# CD_Welder.net
KiCad netlist of a schematic drawn in EAGLE
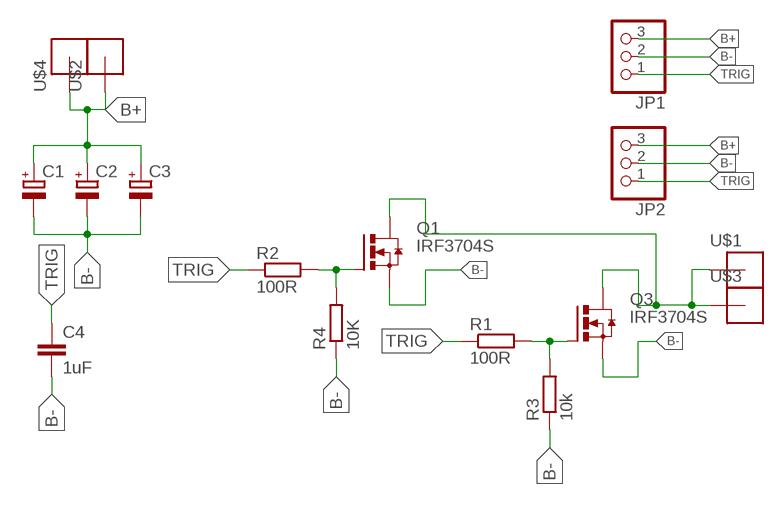
[diagram p0: schematic, sheet 1]

(export (version "E")
  (design (tool "Eeschema 10.0.6"))
  (components
    (comp (ref "C1")
      (value "CPOL-EUE10-30")
      (footprint "eagle-import:EB30D")
      (libsource (lib "eagle-import") (part "CPOL-EUE10-30"))
    )
    (comp (ref "C2")
      (value "CPOL-EUE10-30")
      (footprint "eagle-import:EB30D")
      (libsource (lib "eagle-import") (part "CPOL-EUE10-30"))
    )
    (comp (ref "C3")
      (value "CPOL-EUE10-30")
      (footprint "eagle-import:EB30D")
      (libsource (lib "eagle-import") (part "CPOL-EUE10-30"))
    )
    (comp (ref "C4")
      (value "1uF")
      (footprint "eagle-import:C1206")
      (libsource (lib "eagle-import") (part "C-EUC1206"))
    )
    (comp (ref "JP1")
      (value "PINHD-1X3")
      (footprint "eagle-import:1X03")
      (libsource (lib "eagle-import") (part "PINHD-1X3"))
    )
    (comp (ref "JP2")
      (value "PINHD-1X3")
      (footprint "eagle-import:1X03")
      (libsource (lib "eagle-import") (part "PINHD-1X3"))
    )
    (comp (ref "Q1")
      (value "IRF3704S")
      (footprint "eagle-import:D2PACK")
      (libsource (lib "eagle-import") (part "IRF3704S"))
    )
    (comp (ref "Q3")
      (value "IRF3704S")
      (footprint "eagle-import:D2PACK")
      (libsource (lib "eagle-import") (part "IRF3704S"))
    )
    (comp (ref "R1")
      (value "100R")
      (footprint "eagle-import:R1206")
      (libsource (lib "eagle-import") (part "R-EU_R1206"))
    )
    (comp (ref "R2")
      (value "100R")
      (footprint "eagle-import:R1206")
      (libsource (lib "eagle-import") (part "R-EU_R1206"))
    )
    (comp (ref "R3")
      (value "10k")
      (footprint "eagle-import:R1206")
      (libsource (lib "eagle-import") (part "R-EU_R1206"))
    )
    (comp (ref "R4")
      (value "10K")
      (footprint "eagle-import:R1206")
      (libsource (lib "eagle-import") (part "R-EU_R1206"))
    )
    (comp (ref "U$1")
      (value "BIG_PINHEADX1M4")
      (footprint "eagle-import:M4_PINHEAD")
      (libsource (lib "eagle-import") (part "BIG_PINHEADX1M4"))
    )
    (comp (ref "U$2")
      (value "BIG_PINHEADX1M4")
      (footprint "eagle-import:M4_PINHEAD")
      (libsource (lib "eagle-import") (part "BIG_PINHEADX1M4"))
    )
    (comp (ref "U$3")
      (value "BIG_PINHEADX1M4")
      (footprint "eagle-import:M4_PINHEAD")
      (libsource (lib "eagle-import") (part "BIG_PINHEADX1M4"))
    )
    (comp (ref "U$4")
      (value "BIG_PINHEADX1M4")
      (footprint "eagle-import:M4_PINHEAD")
      (libsource (lib "eagle-import") (part "BIG_PINHEADX1M4"))
    )
  )
  (nets
    (net (code "1") (name "B+") (class "Default")
      (node (ref "C1") (pin "+") (pinfunction "+_+") (pintype "passive"))
      (node (ref "C2") (pin "+") (pinfunction "+_+") (pintype "passive"))
      (node (ref "C3") (pin "+") (pinfunction "+_+") (pintype "passive"))
      (node (ref "JP1") (pin "3") (pinfunction "3_3") (pintype "passive"))
      (node (ref "JP2") (pin "3") (pinfunction "3_3") (pintype "passive"))
      (node (ref "U$2") (pin "P$1") (pinfunction "P$1_P$1") (pintype "bidirectional"))
      (node (ref "U$4") (pin "P$1") (pinfunction "P$1_P$1") (pintype "bidirectional"))
    )
    (net (code "2") (name "B-") (class "Default")
      (node (ref "C1") (pin "-") (pinfunction "-_-") (pintype "passive"))
      (node (ref "C2") (pin "-") (pinfunction "-_-") (pintype "passive"))
      (node (ref "C3") (pin "-") (pinfunction "-_-") (pintype "passive"))
      (node (ref "C4") (pin "2") (pinfunction "2_2") (pintype "passive"))
      (node (ref "JP1") (pin "2") (pinfunction "2_2") (pintype "passive"))
      (node (ref "JP2") (pin "2") (pinfunction "2_2") (pintype "passive"))
      (node (ref "Q1") (pin "3") (pinfunction "S_3") (pintype "passive"))
      (node (ref "Q3") (pin "3") (pinfunction "S_3") (pintype "passive"))
      (node (ref "R3") (pin "1") (pinfunction "1_1") (pintype "passive"))
      (node (ref "R4") (pin "1") (pinfunction "1_1") (pintype "passive"))
    )
    (net (code "3") (name "Net-(Q1-D)") (class "Default")
      (node (ref "Q1") (pin "2") (pinfunction "D_2") (pintype "passive"))
      (node (ref "Q3") (pin "2") (pinfunction "D_2") (pintype "passive"))
      (node (ref "U$1") (pin "P$1") (pinfunction "P$1_P$1") (pintype "bidirectional"))
      (node (ref "U$3") (pin "P$1") (pinfunction "P$1_P$1") (pintype "bidirectional"))
    )
    (net (code "4") (name "Net-(Q1-G)") (class "Default")
      (node (ref "Q1") (pin "1") (pinfunction "G_1") (pintype "passive"))
      (node (ref "R2") (pin "2") (pinfunction "2_2") (pintype "passive"))
      (node (ref "R4") (pin "2") (pinfunction "2_2") (pintype "passive"))
    )
    (net (code "5") (name "Net-(Q3-G)") (class "Default")
      (node (ref "Q3") (pin "1") (pinfunction "G_1") (pintype "passive"))
      (node (ref "R1") (pin "2") (pinfunction "2_2") (pintype "passive"))
      (node (ref "R3") (pin "2") (pinfunction "2_2") (pintype "passive"))
    )
    (net (code "6") (name "TRIG") (class "Default")
      (node (ref "C4") (pin "1") (pinfunction "1_1") (pintype "passive"))
      (node (ref "JP1") (pin "1") (pinfunction "1_1") (pintype "passive"))
      (node (ref "JP2") (pin "1") (pinfunction "1_1") (pintype "passive"))
      (node (ref "R1") (pin "1") (pinfunction "1_1") (pintype "passive"))
      (node (ref "R2") (pin "1") (pinfunction "1_1") (pintype "passive"))
    )
  )
)
